# RadarEyes.net
KiCad netlist of a schematic drawn in EAGLE
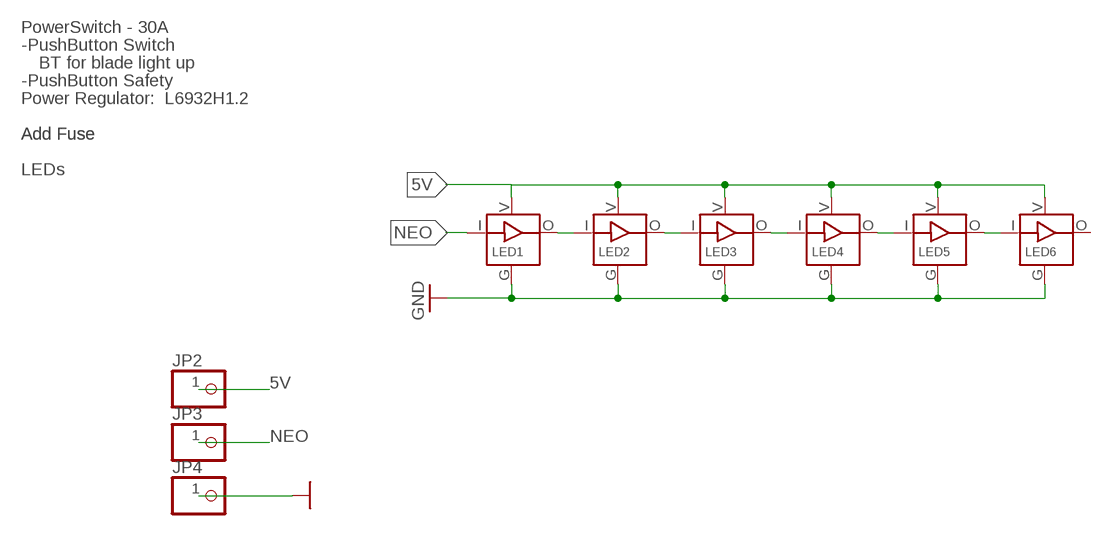
[diagram p0: schematic, sheet 1]

(export (version "E")
  (design (tool "Eeschema 10.0.6"))
  (components
    (comp (ref "JP2")
      (value "PINHD-1X1")
      (footprint "eagle-import:1X01")
      (libsource (lib "eagle-import") (part "PINHD-1X1"))
    )
    (comp (ref "JP3")
      (value "PINHD-1X1")
      (footprint "eagle-import:1X01")
      (libsource (lib "eagle-import") (part "PINHD-1X1"))
    )
    (comp (ref "JP4")
      (value "PINHD-1X1")
      (footprint "eagle-import:1X01")
      (libsource (lib "eagle-import") (part "PINHD-1X1"))
    )
    (comp (ref "LED1")
      (value "SK6812_3535")
      (footprint "eagle-import:LED3535")
      (libsource (lib "eagle-import") (part "SK6812_3535"))
    )
    (comp (ref "LED2")
      (value "SK6812_3535")
      (footprint "eagle-import:LED3535")
      (libsource (lib "eagle-import") (part "SK6812_3535"))
    )
    (comp (ref "LED3")
      (value "SK6812_3535")
      (footprint "eagle-import:LED3535")
      (libsource (lib "eagle-import") (part "SK6812_3535"))
    )
    (comp (ref "LED4")
      (value "SK6812_3535")
      (footprint "eagle-import:LED3535")
      (libsource (lib "eagle-import") (part "SK6812_3535"))
    )
    (comp (ref "LED5")
      (value "SK6812_3535")
      (footprint "eagle-import:LED3535")
      (libsource (lib "eagle-import") (part "SK6812_3535"))
    )
    (comp (ref "LED6")
      (value "SK6812_3535")
      (footprint "eagle-import:LED3535")
      (libsource (lib "eagle-import") (part "SK6812_3535"))
    )
  )
  (nets
    (net (code "1") (name "5V") (class "Default")
      (node (ref "JP2") (pin "1") (pinfunction "1_1") (pintype "passive"))
      (node (ref "LED1") (pin "V") (pinfunction "VDD_V") (pintype "power_in"))
      (node (ref "LED2") (pin "V") (pinfunction "VDD_V") (pintype "power_in"))
      (node (ref "LED3") (pin "V") (pinfunction "VDD_V") (pintype "power_in"))
      (node (ref "LED4") (pin "V") (pinfunction "VDD_V") (pintype "power_in"))
      (node (ref "LED5") (pin "V") (pinfunction "VDD_V") (pintype "power_in"))
      (node (ref "LED6") (pin "V") (pinfunction "VDD_V") (pintype "power_in"))
    )
    (net (code "2") (name "GND") (class "Default")
      (node (ref "JP4") (pin "1") (pinfunction "1_1") (pintype "passive"))
      (node (ref "LED1") (pin "G") (pinfunction "GND_G") (pintype "power_in"))
      (node (ref "LED2") (pin "G") (pinfunction "GND_G") (pintype "power_in"))
      (node (ref "LED3") (pin "G") (pinfunction "GND_G") (pintype "power_in"))
      (node (ref "LED4") (pin "G") (pinfunction "GND_G") (pintype "power_in"))
      (node (ref "LED5") (pin "G") (pinfunction "GND_G") (pintype "power_in"))
      (node (ref "LED6") (pin "G") (pinfunction "GND_G") (pintype "power_in"))
    )
    (net (code "3") (name "NEO") (class "Default")
      (node (ref "JP3") (pin "1") (pinfunction "1_1") (pintype "passive"))
      (node (ref "LED1") (pin "I") (pinfunction "DI_I") (pintype "input"))
    )
    (net (code "4") (name "Net-(LED1-DO)") (class "Default")
      (node (ref "LED1") (pin "O") (pinfunction "DO_O") (pintype "output"))
      (node (ref "LED2") (pin "I") (pinfunction "DI_I") (pintype "input"))
    )
    (net (code "5") (name "Net-(LED2-DO)") (class "Default")
      (node (ref "LED2") (pin "O") (pinfunction "DO_O") (pintype "output"))
      (node (ref "LED3") (pin "I") (pinfunction "DI_I") (pintype "input"))
    )
    (net (code "6") (name "Net-(LED3-DO)") (class "Default")
      (node (ref "LED3") (pin "O") (pinfunction "DO_O") (pintype "output"))
      (node (ref "LED4") (pin "I") (pinfunction "DI_I") (pintype "input"))
    )
    (net (code "7") (name "Net-(LED4-DO)") (class "Default")
      (node (ref "LED4") (pin "O") (pinfunction "DO_O") (pintype "output"))
      (node (ref "LED5") (pin "I") (pinfunction "DI_I") (pintype "input"))
    )
    (net (code "8") (name "Net-(LED5-DO)") (class "Default")
      (node (ref "LED5") (pin "O") (pinfunction "DO_O") (pintype "output"))
      (node (ref "LED6") (pin "I") (pinfunction "DI_I") (pintype "input"))
    )
    (net (code "9") (name "unconnected-(LED6-DO-PadO)") (class "Default")
      (node (ref "LED6") (pin "O") (pinfunction "DO_O") (pintype "output"))
    )
  )
)
